# optical_modul.net
KiCad netlist of a schematic drawn in EAGLE
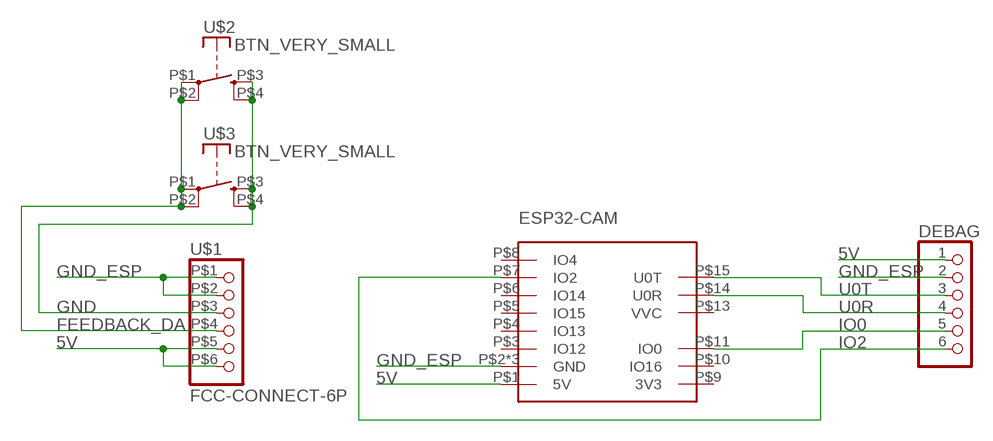
[diagram p0: schematic, sheet 1]

(export (version "E")
  (design (tool "Eeschema 10.0.6"))
  (components
    (comp (ref "DEBAG")
      (value "PINHD-1X6")
      (footprint "eagle-import:1X06")
      (libsource (lib "eagle-import") (part "PINHD-1X6"))
    )
    (comp (ref "ESP32-CAM")
      (value "ESP32-CAM")
      (footprint "eagle-import:ESP32-CAM")
      (libsource (lib "eagle-import") (part "ESP32-CAM"))
    )
    (comp (ref "U$1")
      (value "FCC-CONNECT-6P")
      (footprint "eagle-import:FFC-CONNECT-6P-SMD")
      (libsource (lib "eagle-import") (part "FCC-CONNECT-6P"))
    )
    (comp (ref "U$2")
      (value "BTN_VERY_SMALL")
      (footprint "eagle-import:BTN_VERY_SMALL")
      (libsource (lib "eagle-import") (part "BTN_VERY_SMALL"))
    )
    (comp (ref "U$3")
      (value "BTN_VERY_SMALL")
      (footprint "eagle-import:BTN_VERY_SMALL")
      (libsource (lib "eagle-import") (part "BTN_VERY_SMALL"))
    )
  )
  (nets
    (net (code "1") (name "/5V") (class "Default")
      (node (ref "DEBAG") (pin "1") (pinfunction "1_1") (pintype "passive"))
      (node (ref "ESP32-CAM") (pin "P$1") (pinfunction "5V_P$1") (pintype "bidirectional"))
      (node (ref "U$1") (pin "P$5") (pinfunction "5_P$5") (pintype "passive"))
      (node (ref "U$1") (pin "P$6") (pinfunction "6_P$6") (pintype "passive"))
    )
    (net (code "2") (name "/FEEDBACK_DA") (class "Default")
      (node (ref "U$1") (pin "P$4") (pinfunction "4_P$4") (pintype "passive"))
      (node (ref "U$2") (pin "P$1") (pinfunction "P_P$1") (pintype "passive"))
      (node (ref "U$2") (pin "P$2") (pinfunction "P_P$2") (pintype "passive"))
      (node (ref "U$3") (pin "P$1") (pinfunction "P_P$1") (pintype "passive"))
      (node (ref "U$3") (pin "P$2") (pinfunction "P_P$2") (pintype "passive"))
    )
    (net (code "3") (name "/GND") (class "Default")
      (node (ref "U$1") (pin "P$3") (pinfunction "3_P$3") (pintype "passive"))
      (node (ref "U$2") (pin "P$3") (pinfunction "S_P$3") (pintype "passive"))
      (node (ref "U$2") (pin "P$4") (pinfunction "S_P$4") (pintype "passive"))
      (node (ref "U$3") (pin "P$3") (pinfunction "S_P$3") (pintype "passive"))
      (node (ref "U$3") (pin "P$4") (pinfunction "S_P$4") (pintype "passive"))
    )
    (net (code "4") (name "/GND_ESP") (class "Default")
      (node (ref "DEBAG") (pin "2") (pinfunction "2_2") (pintype "passive"))
      (node (ref "ESP32-CAM") (pin "P$12") (pinfunction "GND_P$12") (pintype "bidirectional"))
      (node (ref "ESP32-CAM") (pin "P$16") (pinfunction "GND_P$16") (pintype "bidirectional"))
      (node (ref "ESP32-CAM") (pin "P$2") (pinfunction "GND_P$2") (pintype "bidirectional"))
      (node (ref "U$1") (pin "P$1") (pinfunction "1_P$1") (pintype "passive"))
      (node (ref "U$1") (pin "P$2") (pinfunction "2_P$2") (pintype "passive"))
    )
    (net (code "5") (name "/IO0") (class "Default")
      (node (ref "DEBAG") (pin "5") (pinfunction "5_5") (pintype "passive"))
      (node (ref "ESP32-CAM") (pin "P$11") (pinfunction "IO0_P$11") (pintype "bidirectional"))
    )
    (net (code "6") (name "/IO2") (class "Default")
      (node (ref "DEBAG") (pin "6") (pinfunction "6_6") (pintype "passive"))
      (node (ref "ESP32-CAM") (pin "P$7") (pinfunction "IO2_P$7") (pintype "bidirectional"))
    )
    (net (code "7") (name "/U0R") (class "Default")
      (node (ref "DEBAG") (pin "4") (pinfunction "4_4") (pintype "passive"))
      (node (ref "ESP32-CAM") (pin "P$14") (pinfunction "U0R_P$14") (pintype "bidirectional"))
    )
    (net (code "8") (name "/U0T") (class "Default")
      (node (ref "DEBAG") (pin "3") (pinfunction "3_3") (pintype "passive"))
      (node (ref "ESP32-CAM") (pin "P$15") (pinfunction "U0T_P$15") (pintype "bidirectional"))
    )
    (net (code "9") (name "unconnected-(ESP32-CAM-3V3-PadP$9)") (class "Default")
      (node (ref "ESP32-CAM") (pin "P$9") (pinfunction "3V3_P$9") (pintype "bidirectional"))
    )
    (net (code "10") (name "unconnected-(ESP32-CAM-IO4-PadP$8)") (class "Default")
      (node (ref "ESP32-CAM") (pin "P$8") (pinfunction "IO4_P$8") (pintype "bidirectional"))
    )
    (net (code "11") (name "unconnected-(ESP32-CAM-IO12-PadP$3)") (class "Default")
      (node (ref "ESP32-CAM") (pin "P$3") (pinfunction "IO12_P$3") (pintype "bidirectional"))
    )
    (net (code "12") (name "unconnected-(ESP32-CAM-IO13-PadP$4)") (class "Default")
      (node (ref "ESP32-CAM") (pin "P$4") (pinfunction "IO13_P$4") (pintype "bidirectional"))
    )
    (net (code "13") (name "unconnected-(ESP32-CAM-IO14-PadP$6)") (class "Default")
      (node (ref "ESP32-CAM") (pin "P$6") (pinfunction "IO14_P$6") (pintype "bidirectional"))
    )
    (net (code "14") (name "unconnected-(ESP32-CAM-IO15-PadP$5)") (class "Default")
      (node (ref "ESP32-CAM") (pin "P$5") (pinfunction "IO15_P$5") (pintype "bidirectional"))
    )
    (net (code "15") (name "unconnected-(ESP32-CAM-IO16-PadP$10)") (class "Default")
      (node (ref "ESP32-CAM") (pin "P$10") (pinfunction "IO16_P$10") (pintype "bidirectional"))
    )
    (net (code "16") (name "unconnected-(ESP32-CAM-VVC-PadP$13)") (class "Default")
      (node (ref "ESP32-CAM") (pin "P$13") (pinfunction "VVC_P$13") (pintype "bidirectional"))
    )
  )
)
